# Infrarojo_01.net
KiCad netlist of a schematic drawn in EAGLE
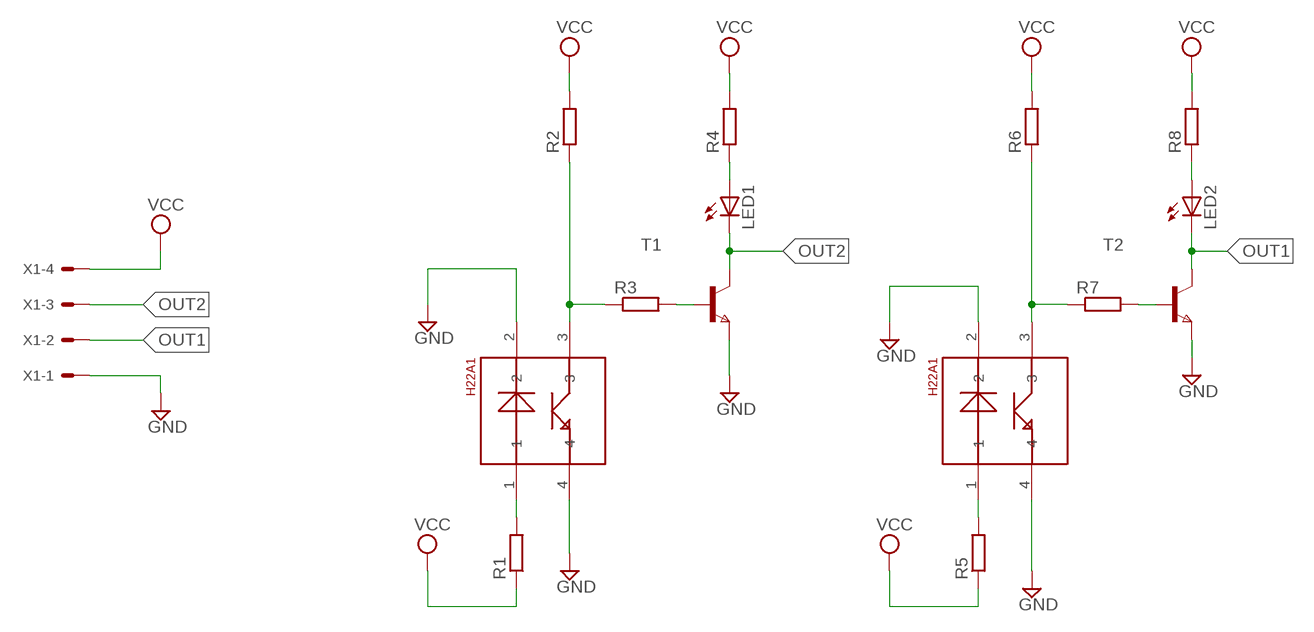
[diagram p0: schematic, sheet 1]

(export (version "E")
  (design (tool "Eeschema 10.0.6"))
  (components
    (comp (ref "IR1")
      (value "IR1")
      (footprint "eagle-import:H22A1")
      (libsource (lib "eagle-import") (part "H22A1"))
    )
    (comp (ref "IR2")
      (value "IR2")
      (footprint "eagle-import:H22A1")
      (libsource (lib "eagle-import") (part "H22A1"))
    )
    (comp (ref "LED1")
      (value "LED3MM")
      (footprint "eagle-import:LED3MM")
      (libsource (lib "eagle-import") (part "LED3MM"))
    )
    (comp (ref "LED2")
      (value "LED3MM")
      (footprint "eagle-import:LED3MM")
      (libsource (lib "eagle-import") (part "LED3MM"))
    )
    (comp (ref "R1")
      (value "R-EU_R0805")
      (footprint "eagle-import:R0805")
      (libsource (lib "eagle-import") (part "R-EU_R0805"))
    )
    (comp (ref "R2")
      (value "R-EU_R0805")
      (footprint "eagle-import:R0805")
      (libsource (lib "eagle-import") (part "R-EU_R0805"))
    )
    (comp (ref "R3")
      (value "R-EU_R0805")
      (footprint "eagle-import:R0805")
      (libsource (lib "eagle-import") (part "R-EU_R0805"))
    )
    (comp (ref "R4")
      (value "R-EU_R0805")
      (footprint "eagle-import:R0805")
      (libsource (lib "eagle-import") (part "R-EU_R0805"))
    )
    (comp (ref "R5")
      (value "R-EU_R0805")
      (footprint "eagle-import:R0805")
      (libsource (lib "eagle-import") (part "R-EU_R0805"))
    )
    (comp (ref "R6")
      (value "R-EU_R0805")
      (footprint "eagle-import:R0805")
      (libsource (lib "eagle-import") (part "R-EU_R0805"))
    )
    (comp (ref "R7")
      (value "R-EU_R0805")
      (footprint "eagle-import:R0805")
      (libsource (lib "eagle-import") (part "R-EU_R0805"))
    )
    (comp (ref "R8")
      (value "R-EU_R0805")
      (footprint "eagle-import:R0805")
      (libsource (lib "eagle-import") (part "R-EU_R0805"))
    )
    (comp (ref "T1")
      (value "NPNSOT23")
      (footprint "eagle-import:SOT-23")
      (fields (field (name "MPN") "DSS20201L-7"))
      (libsource (lib "eagle-import") (part "NPNSOT23"))
    )
    (comp (ref "T2")
      (value "NPNSOT23")
      (footprint "eagle-import:SOT-23")
      (fields (field (name "MPN") "DSS20201L-7"))
      (libsource (lib "eagle-import") (part "NPNSOT23"))
    )
    (comp (ref "X1")
      (value "C-GRID-04-70543")
      (footprint "eagle-import:70543-04")
      (fields (field (name "MF") "MOLEX"))
      (libsource (lib "eagle-import") (part "C-GRID-04-70543"))
    )
  )
  (nets
    (net (code "1") (name "GND") (class "Default")
      (node (ref "IR1") (pin "2") (pinfunction "2_2") (pintype "bidirectional"))
      (node (ref "IR1") (pin "4") (pinfunction "4_4") (pintype "bidirectional"))
      (node (ref "IR2") (pin "2") (pinfunction "2_2") (pintype "bidirectional"))
      (node (ref "IR2") (pin "4") (pinfunction "4_4") (pintype "bidirectional"))
      (node (ref "T1") (pin "2") (pinfunction "E_2") (pintype "passive"))
      (node (ref "T2") (pin "2") (pinfunction "E_2") (pintype "passive"))
      (node (ref "X1") (pin "1") (pinfunction "S_1") (pintype "passive"))
    )
    (net (code "2") (name "Net-(IR1-Pad1)") (class "Default")
      (node (ref "IR1") (pin "1") (pinfunction "1_1") (pintype "bidirectional"))
      (node (ref "R1") (pin "2") (pinfunction "2_2") (pintype "passive"))
    )
    (net (code "3") (name "Net-(IR1-Pad3)") (class "Default")
      (node (ref "IR1") (pin "3") (pinfunction "3_3") (pintype "bidirectional"))
      (node (ref "R2") (pin "1") (pinfunction "1_1") (pintype "passive"))
      (node (ref "R3") (pin "1") (pinfunction "1_1") (pintype "passive"))
    )
    (net (code "4") (name "Net-(IR2-Pad1)") (class "Default")
      (node (ref "IR2") (pin "1") (pinfunction "1_1") (pintype "bidirectional"))
      (node (ref "R5") (pin "2") (pinfunction "2_2") (pintype "passive"))
    )
    (net (code "5") (name "Net-(IR2-Pad3)") (class "Default")
      (node (ref "IR2") (pin "3") (pinfunction "3_3") (pintype "bidirectional"))
      (node (ref "R6") (pin "1") (pinfunction "1_1") (pintype "passive"))
      (node (ref "R7") (pin "1") (pinfunction "1_1") (pintype "passive"))
    )
    (net (code "6") (name "Net-(LED1-PadA)") (class "Default")
      (node (ref "LED1") (pin "A") (pinfunction "A_A") (pintype "passive"))
      (node (ref "R4") (pin "1") (pinfunction "1_1") (pintype "passive"))
    )
    (net (code "7") (name "Net-(LED2-PadA)") (class "Default")
      (node (ref "LED2") (pin "A") (pinfunction "A_A") (pintype "passive"))
      (node (ref "R8") (pin "1") (pinfunction "1_1") (pintype "passive"))
    )
    (net (code "8") (name "Net-(T1-B)") (class "Default")
      (node (ref "R3") (pin "2") (pinfunction "2_2") (pintype "passive"))
      (node (ref "T1") (pin "3") (pinfunction "B_3") (pintype "passive"))
    )
    (net (code "9") (name "Net-(T2-B)") (class "Default")
      (node (ref "R7") (pin "2") (pinfunction "2_2") (pintype "passive"))
      (node (ref "T2") (pin "3") (pinfunction "B_3") (pintype "passive"))
    )
    (net (code "10") (name "OUT1") (class "Default")
      (node (ref "LED2") (pin "K") (pinfunction "C_K") (pintype "passive"))
      (node (ref "T2") (pin "1") (pinfunction "C_1") (pintype "passive"))
      (node (ref "X1") (pin "2") (pinfunction "S_2") (pintype "passive"))
    )
    (net (code "11") (name "OUT2") (class "Default")
      (node (ref "LED1") (pin "K") (pinfunction "C_K") (pintype "passive"))
      (node (ref "T1") (pin "1") (pinfunction "C_1") (pintype "passive"))
      (node (ref "X1") (pin "3") (pinfunction "S_3") (pintype "passive"))
    )
    (net (code "12") (name "VCC") (class "Default")
      (node (ref "R1") (pin "1") (pinfunction "1_1") (pintype "passive"))
      (node (ref "R2") (pin "2") (pinfunction "2_2") (pintype "passive"))
      (node (ref "R4") (pin "2") (pinfunction "2_2") (pintype "passive"))
      (node (ref "R5") (pin "1") (pinfunction "1_1") (pintype "passive"))
      (node (ref "R6") (pin "2") (pinfunction "2_2") (pintype "passive"))
      (node (ref "R8") (pin "2") (pinfunction "2_2") (pintype "passive"))
      (node (ref "X1") (pin "4") (pinfunction "S_4") (pintype "passive"))
    )
  )
)
